# easyeda_schematic.net
KiCad netlist of a schematic drawn in EasyEDA
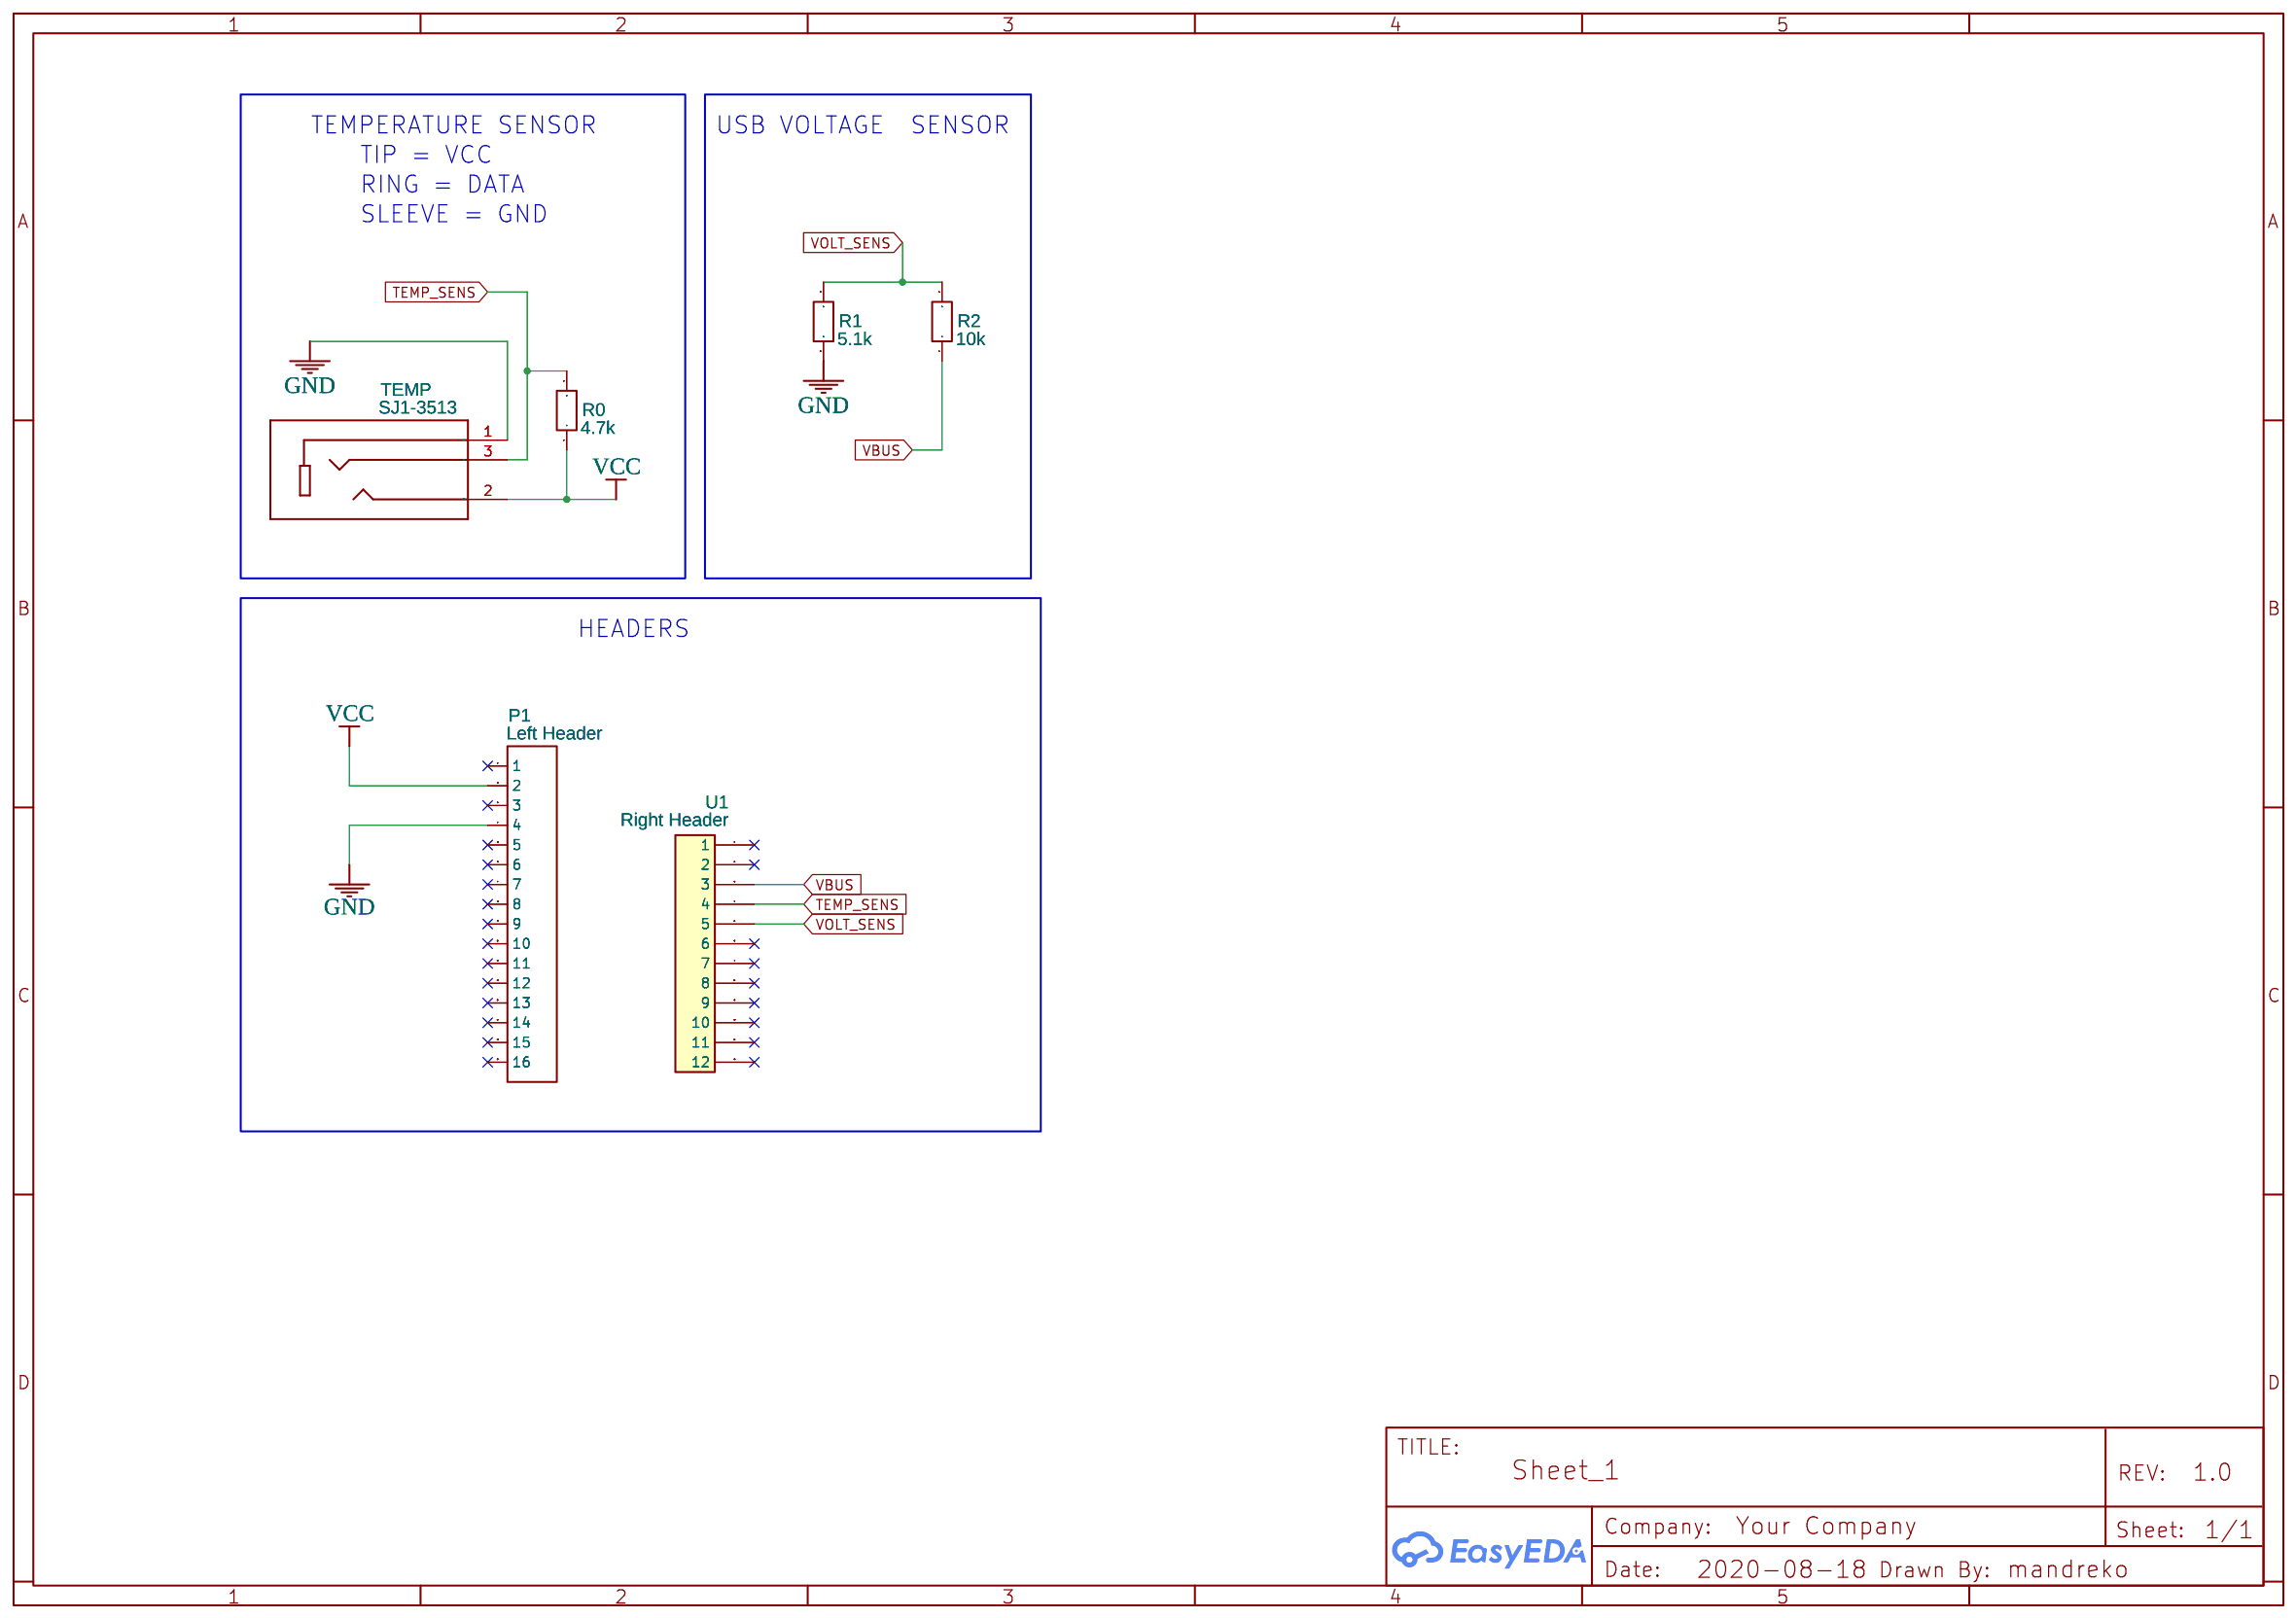
[diagram p0: schematic sheet]

(export (version "E")
  (design (tool "Eeschema 10.0.6"))
  (components
    (comp (ref "P1")
      (value "Left Header")
      (fields
        (field (name "BOM_Manufacturer Part") "Female header1*16P pitch 2.54mm")
        (field (name "BOM_Supplier Part") "C66987")
      )
      (libsource (lib "") (part "Header-Female-2.54_1x16"))
    )
    (comp (ref "R0") (value "4.7k") (libsource (lib "") (part "R_0603_EU")))
    (comp (ref "R1") (value "5.1k") (libsource (lib "") (part "R_0603_EU")))
    (comp (ref "R2") (value "10k") (libsource (lib "") (part "R_0603_EU")))
    (comp (ref "TEMP") (value "SJ1-3513") (libsource (lib "") (part "SJ1-3513")))
    (comp (ref "U1")
      (value "Right Header")
      (fields (field (name "BOM_Manufacturer Part") "Header-Male-2.54_1x12"))
      (libsource (lib "") (part "Header-Male-2.54_1x12"))
    )
  )
  (nets
    (net (code "1") (name "GND") (class "Default")
      (node (ref "P1") (pin "4") (pinfunction "4_4") (pintype "input"))
      (node (ref "R1") (pin "1") (pinfunction "1_1") (pintype "unspecified"))
      (node (ref "TEMP") (pin "1") (pinfunction "1_1") (pintype "bidirectional"))
    )
    (net (code "2") (name "TEMP_SENS") (class "Default")
      (node (ref "R0") (pin "2") (pinfunction "2_2") (pintype "unspecified"))
      (node (ref "TEMP") (pin "3") (pinfunction "3_3") (pintype "bidirectional"))
      (node (ref "U1") (pin "4") (pinfunction "4_4") (pintype "input"))
    )
    (net (code "3") (name "VBUS") (class "Default")
      (node (ref "R2") (pin "1") (pinfunction "1_1") (pintype "unspecified"))
      (node (ref "U1") (pin "3") (pinfunction "3_3") (pintype "input"))
    )
    (net (code "4") (name "VCC") (class "Default")
      (node (ref "P1") (pin "2") (pinfunction "2_2") (pintype "input"))
      (node (ref "R0") (pin "1") (pinfunction "1_1") (pintype "unspecified"))
      (node (ref "TEMP") (pin "2") (pinfunction "2_2") (pintype "bidirectional"))
    )
    (net (code "5") (name "VOLT_SENS") (class "Default")
      (node (ref "R1") (pin "2") (pinfunction "2_2") (pintype "unspecified"))
      (node (ref "R2") (pin "2") (pinfunction "2_2") (pintype "unspecified"))
      (node (ref "U1") (pin "5") (pinfunction "5_5") (pintype "input"))
    )
    (net (code "6") (name "unconnected-(P1-Pad1)") (class "Default")
      (node (ref "P1") (pin "1") (pinfunction "1_1") (pintype "input+no_connect"))
    )
    (net (code "7") (name "unconnected-(P1-Pad3)") (class "Default")
      (node (ref "P1") (pin "3") (pinfunction "3_3") (pintype "input+no_connect"))
    )
    (net (code "8") (name "unconnected-(P1-Pad5)") (class "Default")
      (node (ref "P1") (pin "5") (pinfunction "5_5") (pintype "input+no_connect"))
    )
    (net (code "9") (name "unconnected-(P1-Pad6)") (class "Default")
      (node (ref "P1") (pin "6") (pinfunction "6_6") (pintype "input+no_connect"))
    )
    (net (code "10") (name "unconnected-(P1-Pad7)") (class "Default")
      (node (ref "P1") (pin "7") (pinfunction "7_7") (pintype "input+no_connect"))
    )
    (net (code "11") (name "unconnected-(P1-Pad8)") (class "Default")
      (node (ref "P1") (pin "8") (pinfunction "8_8") (pintype "input+no_connect"))
    )
    (net (code "12") (name "unconnected-(P1-Pad9)") (class "Default")
      (node (ref "P1") (pin "9") (pinfunction "9_9") (pintype "input+no_connect"))
    )
    (net (code "13") (name "unconnected-(P1-Pad10)") (class "Default")
      (node (ref "P1") (pin "10") (pinfunction "10_10") (pintype "input+no_connect"))
    )
    (net (code "14") (name "unconnected-(P1-Pad11)") (class "Default")
      (node (ref "P1") (pin "11") (pinfunction "11_11") (pintype "input+no_connect"))
    )
    (net (code "15") (name "unconnected-(P1-Pad12)") (class "Default")
      (node (ref "P1") (pin "12") (pinfunction "12_12") (pintype "input+no_connect"))
    )
    (net (code "16") (name "unconnected-(P1-Pad13)") (class "Default")
      (node (ref "P1") (pin "13") (pinfunction "13_13") (pintype "input+no_connect"))
    )
    (net (code "17") (name "unconnected-(P1-Pad14)") (class "Default")
      (node (ref "P1") (pin "14") (pinfunction "14_14") (pintype "input+no_connect"))
    )
    (net (code "18") (name "unconnected-(P1-Pad15)") (class "Default")
      (node (ref "P1") (pin "15") (pinfunction "15_15") (pintype "input+no_connect"))
    )
    (net (code "19") (name "unconnected-(P1-Pad16)") (class "Default")
      (node (ref "P1") (pin "16") (pinfunction "16_16") (pintype "input+no_connect"))
    )
    (net (code "20") (name "unconnected-(U1-Pad1)") (class "Default")
      (node (ref "U1") (pin "1") (pinfunction "1_1") (pintype "input+no_connect"))
    )
    (net (code "21") (name "unconnected-(U1-Pad2)") (class "Default")
      (node (ref "U1") (pin "2") (pinfunction "2_2") (pintype "input+no_connect"))
    )
    (net (code "22") (name "unconnected-(U1-Pad6)") (class "Default")
      (node (ref "U1") (pin "6") (pinfunction "6_6") (pintype "input+no_connect"))
    )
    (net (code "23") (name "unconnected-(U1-Pad7)") (class "Default")
      (node (ref "U1") (pin "7") (pinfunction "7_7") (pintype "input+no_connect"))
    )
    (net (code "24") (name "unconnected-(U1-Pad8)") (class "Default")
      (node (ref "U1") (pin "8") (pinfunction "8_8") (pintype "input+no_connect"))
    )
    (net (code "25") (name "unconnected-(U1-Pad9)") (class "Default")
      (node (ref "U1") (pin "9") (pinfunction "9_9") (pintype "input+no_connect"))
    )
    (net (code "26") (name "unconnected-(U1-Pad10)") (class "Default")
      (node (ref "U1") (pin "10") (pinfunction "10_10") (pintype "input+no_connect"))
    )
    (net (code "27") (name "unconnected-(U1-Pad11)") (class "Default")
      (node (ref "U1") (pin "11") (pinfunction "11_11") (pintype "input+no_connect"))
    )
    (net (code "28") (name "unconnected-(U1-Pad12)") (class "Default")
      (node (ref "U1") (pin "12") (pinfunction "12_12") (pintype "input+no_connect"))
    )
  )
)
